# Sheet2.net
KiCad netlist of a schematic drawn in Altium Designer
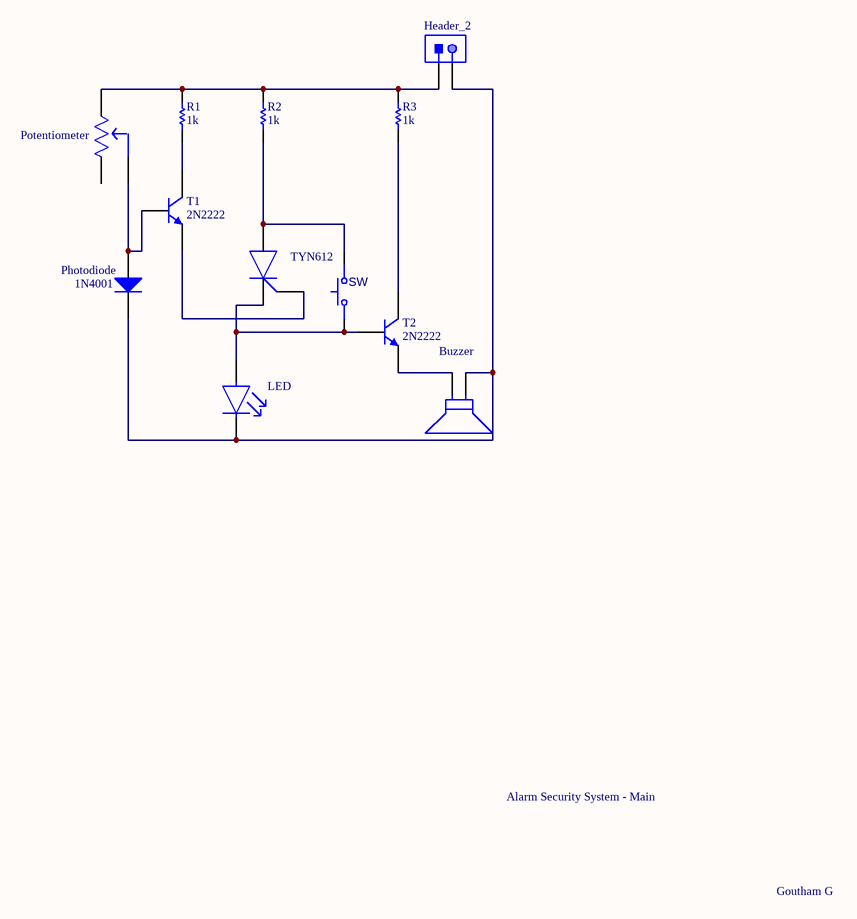
[diagram p0: Sheet2.SchDoc]

(export (version "E")
  (design (tool "Eeschema 10.0.6"))
  (components
    (comp (ref "100K")
      (value "Potentiometer")
      (footprint "FP-3266W-MFG")
      (description "TRIMMER 100K OHM 0.25W PC PIN TOP")
      (fields
        (field (name "MANUFACTURER") "Bourns")
        (field (name "OCTOPART") "https://octopart.com/3266w-1-103lf-bourns-81445")
      )
      (libsource (lib "Altium Content Vault") (part "5aa38b60e553f01fbee9df648f8b81b"))
    )
    (comp (ref "Buzzer")
      (value "Buzzer")
      (footprint "FP-PKM22EPPH4001-B0-MFG")
      (description "AUDIO PIEZO TRANSDUCER 30V TH")
      (libsource (lib "Altium Content Vault") (part "5f581d31613f872430949aa526fd155"))
    )
    (comp (ref "Header_2")
      (value "B2P-VH(LF)(SN)")
      (footprint "JST-B2P-VH(LF)(SN)_V")
      (fields (field (name "MANUFACTURER") "JST"))
      (libsource (lib "GOUTHAM GANESH KUMAR") (part "CN-1P-M-R2"))
    )
    (comp (ref "LED")
      (value "LED")
      (footprint "FP-HLMP-1719-MFG")
      (description "LED YELLOW DIFFUSED T-1 T/H")
      (fields
        (field (name "MANUFACTURER") "Broadcom")
        (field (name "OCTOPART") "https://octopart.com/hlmp-1719-broadcom-71130405")
      )
      (libsource (lib "Altium Content Vault") (part "8706943c75ba83719d021d2fdc84c58"))
    )
    (comp (ref "Photodiode")
      (value "1N4001")
      (footprint "DIOD-DO-41-P-2_V")
      (description "1.0 A Rectifier, 15 pF, 50 V, -65 to 150 degC, 2-Pin DO-41 Plastic, RoHS, Tape and Reel")
      (fields (field (name "MANUFACTURER") "Diodes Inc"))
      (libsource (lib "Altium Content Vault") (part "DIOD-D-A1K2-2"))
    )
    (comp (ref "R1")
      (value "1k")
      (footprint "RESC2013X70X40ML20T20")
      (description "Chip Resistor, 1 KOhm, +/- 1%, 0.125 W, -55 to 155 degC, 0805 (2013 Metric)")
      (fields (field (name "TOLERANCE") "1%") (field (name "POWER") "125mW"))
      (libsource (lib "GOUTHAM GANESH KUMAR") (part "RES-2"))
    )
    (comp (ref "R2")
      (value "1k")
      (footprint "RESC2013X70X40ML20T20")
      (description "Chip Resistor, 1 KOhm, +/- 1%, 0.125 W, -55 to 155 degC, 0805 (2013 Metric)")
      (fields (field (name "TOLERANCE") "1%") (field (name "POWER") "125mW"))
      (libsource (lib "GOUTHAM GANESH KUMAR") (part "RES-2"))
    )
    (comp (ref "R3")
      (value "1k")
      (footprint "RESC2013X70X40ML20T20")
      (description "Chip Resistor, 1 KOhm, +/- 1%, 0.125 W, -55 to 155 degC, 0805 (2013 Metric)")
      (fields (field (name "TOLERANCE") "1%") (field (name "POWER") "125mW"))
      (libsource (lib "GOUTHAM GANESH KUMAR") (part "RES-2"))
    )
    (comp (ref "SW")
      (value "~")
      (footprint "OMRON-B3U-1000P-2-B_V")
      (libsource (lib "GOUTHAM GANESH KUMAR") (part "CMP-00164-6"))
    )
    (comp (ref "T1")
      (value "2N2222")
      (footprint "MLTC-TO-18-3")
      (description "Low Power Bipolar NPN Transistor, 30 V, -65 to 200 degC, 3-Pin TO-18, RoHS, Bulk")
      (fields (field (name "MANUFACTURER") "Multicomp"))
      (libsource (lib "Altium Content Vault") (part "BJT-NPN-EBC-3"))
    )
    (comp (ref "T2")
      (value "2N2222")
      (footprint "MLTC-TO-18-3")
      (description "Low Power Bipolar NPN Transistor, 30 V, -65 to 200 degC, 3-Pin TO-18, RoHS, Bulk")
      (fields (field (name "MANUFACTURER") "Multicomp"))
      (libsource (lib "Altium Content Vault") (part "BJT-NPN-EBC-3"))
    )
    (comp (ref "TYN612")
      (value "TYN612")
      (footprint "SIP450W75P254L1000H1920Q3_PRSS0003AF-A_N")
      (libsource (lib "Altium Content Vault") (part "5e9e9c1ad5e5e757f664e1ab19bc20f"))
    )
  )
  (nets
    (net (code "1") (name "Net-(100K-CCW)") (class "Default")
      (node (ref "100K") (pin "1") (pinfunction "CCW_1") (pintype "passive"))
      (node (ref "Header_2") (pin "1") (pinfunction "1_1") (pintype "passive"))
      (node (ref "R1") (pin "2") (pinfunction "2_2") (pintype "passive"))
      (node (ref "R2") (pin "2") (pinfunction "2_2") (pintype "passive"))
      (node (ref "R3") (pin "2") (pinfunction "2_2") (pintype "passive"))
    )
    (net (code "2") (name "Net-(100K-WIPER)") (class "Default")
      (node (ref "100K") (pin "2") (pinfunction "WIPER_2") (pintype "passive"))
      (node (ref "Photodiode") (pin "1") (pinfunction "A_1") (pintype "passive"))
      (node (ref "T1") (pin "2") (pinfunction "B_2") (pintype "passive"))
    )
    (net (code "3") (name "Net-(LED-A)") (class "Default")
      (node (ref "LED") (pin "2") (pinfunction "A_2") (pintype "passive"))
      (node (ref "SW") (pin "1") (pinfunction "1_1") (pintype "passive"))
      (node (ref "T2") (pin "2") (pinfunction "B_2") (pintype "passive"))
      (node (ref "TYN612") (pin "1") (pinfunction "CATHODE_1") (pintype "passive"))
    )
    (net (code "4") (name "Net-(LED-C)") (class "Default")
      (node (ref "Buzzer") (pin "1") (pinfunction "1_1") (pintype "passive"))
      (node (ref "Header_2") (pin "2") (pinfunction "2_2") (pintype "passive"))
      (node (ref "LED") (pin "1") (pinfunction "C_1") (pintype "passive"))
      (node (ref "Photodiode") (pin "2") (pinfunction "K_2") (pintype "passive"))
    )
    (net (code "5") (name "Net-(T1-C)") (class "Default")
      (node (ref "R1") (pin "1") (pinfunction "1_1") (pintype "passive"))
      (node (ref "T1") (pin "3") (pinfunction "C_3") (pintype "passive"))
    )
    (net (code "6") (name "Net-(T1-E)") (class "Default")
      (node (ref "T1") (pin "1") (pinfunction "E_1") (pintype "passive"))
      (node (ref "TYN612") (pin "3") (pinfunction "GATE_3") (pintype "passive"))
    )
    (net (code "7") (name "Net-(T2-C)") (class "Default")
      (node (ref "R3") (pin "1") (pinfunction "1_1") (pintype "passive"))
      (node (ref "T2") (pin "3") (pinfunction "C_3") (pintype "passive"))
    )
    (net (code "8") (name "Net-(T2-E)") (class "Default")
      (node (ref "Buzzer") (pin "2") (pinfunction "2_2") (pintype "passive"))
      (node (ref "T2") (pin "1") (pinfunction "E_1") (pintype "passive"))
    )
    (net (code "9") (name "Net-(TYN612-ANODE)") (class "Default")
      (node (ref "R2") (pin "1") (pinfunction "1_1") (pintype "passive"))
      (node (ref "SW") (pin "2") (pinfunction "2_2") (pintype "passive"))
      (node (ref "TYN612") (pin "2") (pinfunction "ANODE_2") (pintype "passive"))
    )
    (net (code "10") (name "unconnected-(100K-CW-Pad3)") (class "Default")
      (node (ref "100K") (pin "3") (pinfunction "CW_3") (pintype "passive"))
    )
  )
)
